# restador.net
KiCad netlist of a schematic drawn in Altium Designer
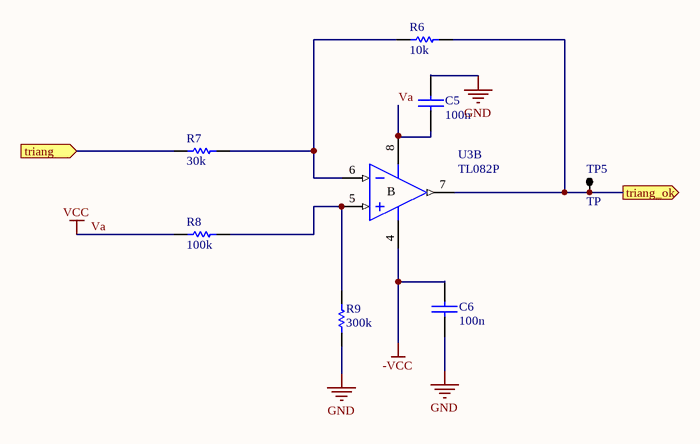
[diagram p0: restador.SchDoc]

(export (version "E")
  (design (tool "Eeschema 10.0.6"))
  (components
    (comp (ref "C5") (value "100n") (footprint "0805") (libsource (lib "LIBEBAL") (part "CAP")))
    (comp (ref "C6") (value "100n") (footprint "0805") (libsource (lib "LIBEBAL") (part "CAP")))
    (comp (ref "R6") (value "10k") (footprint "0805") (libsource (lib "LIBEBAL") (part "RES")))
    (comp (ref "R7") (value "30k") (footprint "0805") (libsource (lib "LIBEBAL") (part "RES")))
    (comp (ref "R8") (value "100k") (footprint "0805") (libsource (lib "LIBEBAL") (part "RES")))
    (comp (ref "R9") (value "300k") (footprint "0805") (libsource (lib "LIBEBAL") (part "RES")))
    (comp (ref "TP5") (value "TP") (footprint "TPTH") (libsource (lib "LIBEBAL") (part "TP")))
    (comp (ref "U3")
      (value "TL082P")
      (footprint "P008")
      (description "JFET-Input Operational Amplifier")
      (fields (field (name "PUBLISHER") "Altium Limited"))
      (libsource (lib "TI Operational Amplifier") (part "TL082P"))
    )
  )
  (nets
    (net (code "1") (name "-VCC") (class "Default")
      (node (ref "C6") (pin "1") (pinfunction "1_1") (pintype "passive"))
      (node (ref "U3") (pin "4") (pinfunction "V-_4") (pintype "power_in"))
    )
    (net (code "2") (name "/triang") (class "Default")
      (node (ref "R7") (pin "1") (pinfunction "1_1") (pintype "passive"))
    )
    (net (code "3") (name "/triang_ok") (class "Default")
      (node (ref "R6") (pin "2") (pinfunction "2_2") (pintype "passive"))
      (node (ref "TP5") (pin "1") (pinfunction "1_1") (pintype "passive"))
      (node (ref "U3") (pin "7") (pinfunction "OUT_7") (pintype "output"))
    )
    (net (code "4") (name "GND") (class "Default")
      (node (ref "C5") (pin "1") (pinfunction "1_1") (pintype "passive"))
      (node (ref "C6") (pin "2") (pinfunction "2_2") (pintype "passive"))
      (node (ref "R9") (pin "1") (pinfunction "1_1") (pintype "passive"))
    )
    (net (code "5") (name "Net-(U3B-IN+)") (class "Default")
      (node (ref "R8") (pin "2") (pinfunction "2_2") (pintype "passive"))
      (node (ref "R9") (pin "2") (pinfunction "2_2") (pintype "passive"))
      (node (ref "U3") (pin "5") (pinfunction "IN+_5") (pintype "input"))
    )
    (net (code "6") (name "Net-(U3B-IN-)") (class "Default")
      (node (ref "R6") (pin "1") (pinfunction "1_1") (pintype "passive"))
      (node (ref "R7") (pin "2") (pinfunction "2_2") (pintype "passive"))
      (node (ref "U3") (pin "6") (pinfunction "IN-_6") (pintype "input"))
    )
    (net (code "7") (name "VCC") (class "Default")
      (node (ref "C5") (pin "2") (pinfunction "2_2") (pintype "passive"))
      (node (ref "R8") (pin "1") (pinfunction "1_1") (pintype "passive"))
      (node (ref "U3") (pin "8") (pinfunction "V+_8") (pintype "power_in"))
    )
  )
)
